# RPI3_LVDS.net
KiCad netlist of a schematic drawn in EAGLE
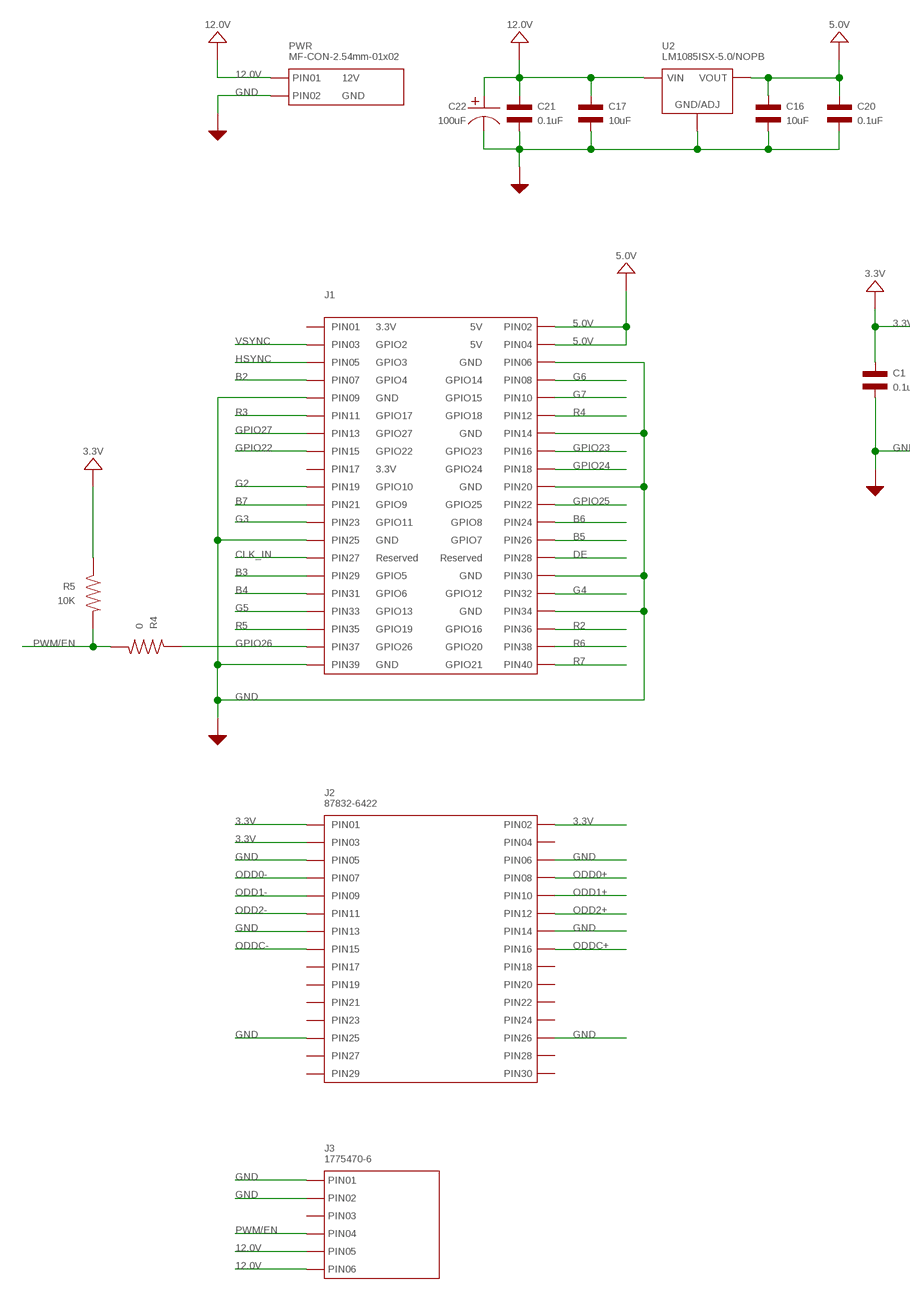
[diagram p0: schematic, sheet 1, part 1 of 2]
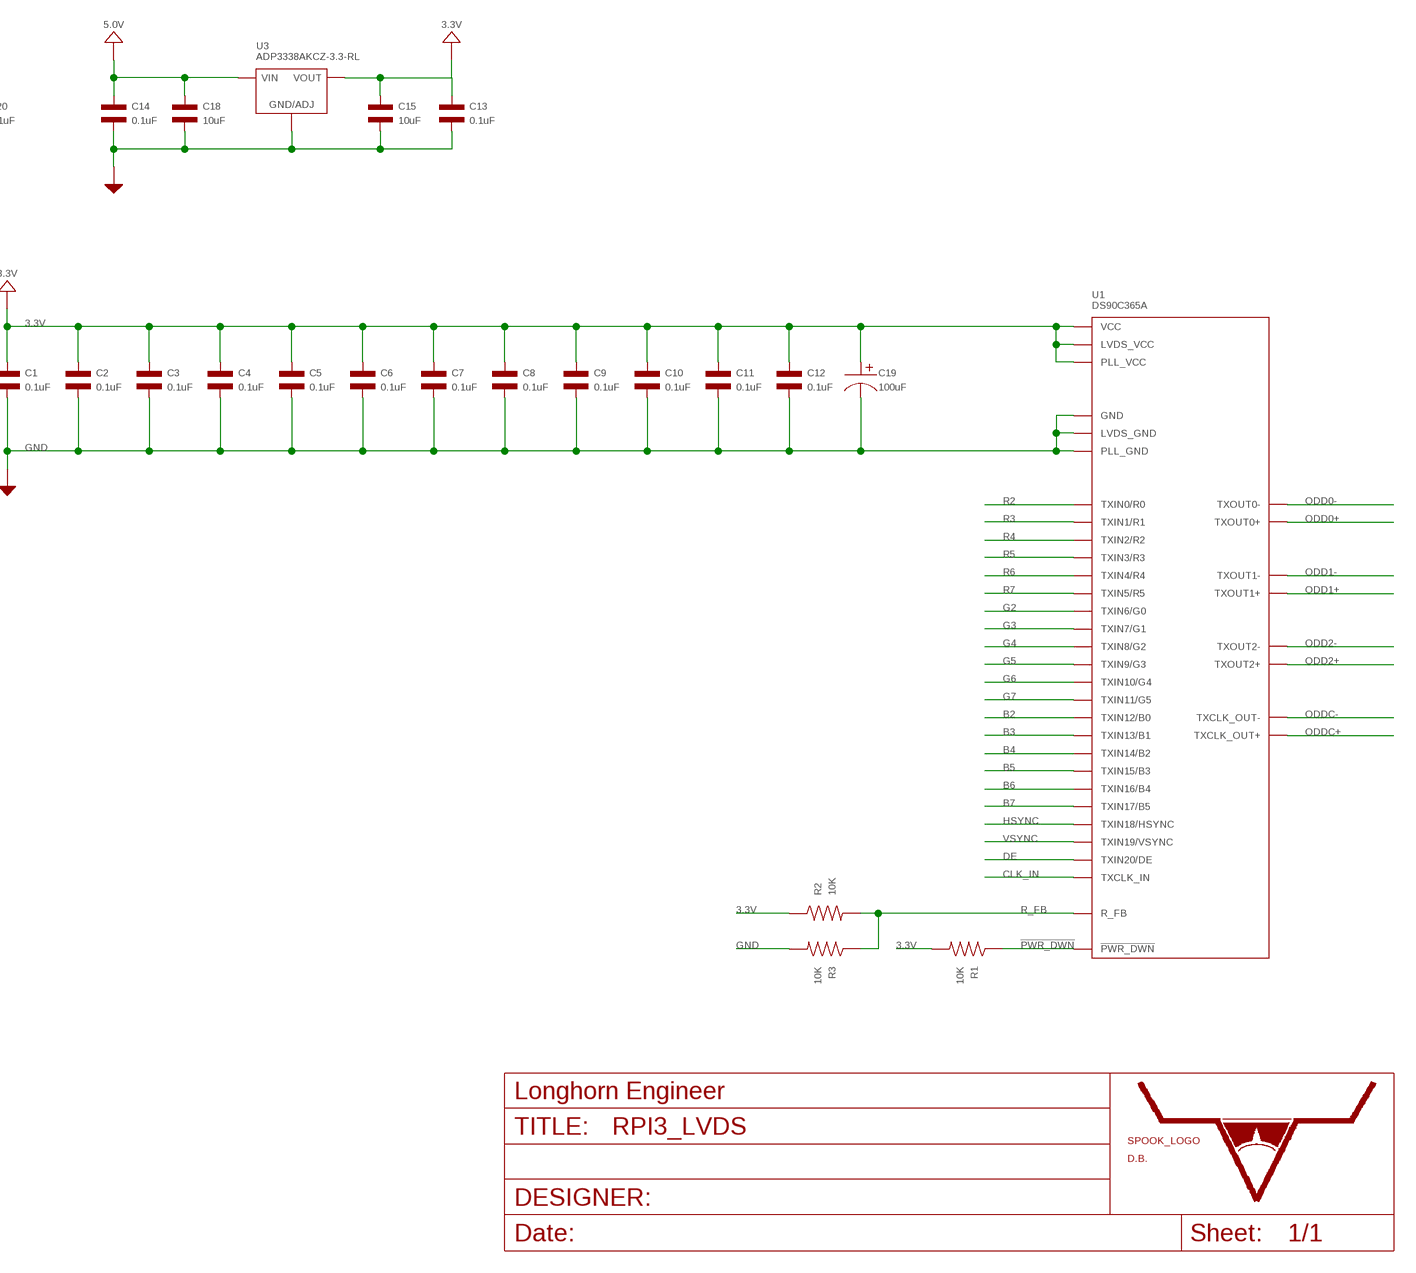
[diagram p1: schematic, sheet 1, part 2 of 2]

(export (version "E")
  (design (tool "Eeschema 10.0.6"))
  (components
    (comp (ref "C1")
      (value "0.1uF")
      (footprint "eagle-import:C0603")
      (libsource (lib "eagle-import") (part "CAPACITOR_NP_0603"))
    )
    (comp (ref "C2")
      (value "0.1uF")
      (footprint "eagle-import:C0603")
      (libsource (lib "eagle-import") (part "CAPACITOR_NP_0603"))
    )
    (comp (ref "C3")
      (value "0.1uF")
      (footprint "eagle-import:C0603")
      (libsource (lib "eagle-import") (part "CAPACITOR_NP_0603"))
    )
    (comp (ref "C4")
      (value "0.1uF")
      (footprint "eagle-import:C0603")
      (libsource (lib "eagle-import") (part "CAPACITOR_NP_0603"))
    )
    (comp (ref "C5")
      (value "0.1uF")
      (footprint "eagle-import:C0603")
      (libsource (lib "eagle-import") (part "CAPACITOR_NP_0603"))
    )
    (comp (ref "C6")
      (value "0.1uF")
      (footprint "eagle-import:C0603")
      (libsource (lib "eagle-import") (part "CAPACITOR_NP_0603"))
    )
    (comp (ref "C7")
      (value "0.1uF")
      (footprint "eagle-import:C0603")
      (libsource (lib "eagle-import") (part "CAPACITOR_NP_0603"))
    )
    (comp (ref "C8")
      (value "0.1uF")
      (footprint "eagle-import:C0603")
      (libsource (lib "eagle-import") (part "CAPACITOR_NP_0603"))
    )
    (comp (ref "C9")
      (value "0.1uF")
      (footprint "eagle-import:C0603")
      (libsource (lib "eagle-import") (part "CAPACITOR_NP_0603"))
    )
    (comp (ref "C10")
      (value "0.1uF")
      (footprint "eagle-import:C0603")
      (libsource (lib "eagle-import") (part "CAPACITOR_NP_0603"))
    )
    (comp (ref "C11")
      (value "0.1uF")
      (footprint "eagle-import:C0603")
      (libsource (lib "eagle-import") (part "CAPACITOR_NP_0603"))
    )
    (comp (ref "C12")
      (value "0.1uF")
      (footprint "eagle-import:C0603")
      (libsource (lib "eagle-import") (part "CAPACITOR_NP_0603"))
    )
    (comp (ref "C13")
      (value "0.1uF")
      (footprint "eagle-import:C0603")
      (libsource (lib "eagle-import") (part "CAPACITOR_NP_0603"))
    )
    (comp (ref "C14")
      (value "0.1uF")
      (footprint "eagle-import:C0603")
      (libsource (lib "eagle-import") (part "CAPACITOR_NP_0603"))
    )
    (comp (ref "C15")
      (value "10uF")
      (footprint "eagle-import:C1206")
      (libsource (lib "eagle-import") (part "CAPACITOR_NP_1206"))
    )
    (comp (ref "C16")
      (value "10uF")
      (footprint "eagle-import:C1206")
      (libsource (lib "eagle-import") (part "CAPACITOR_NP_1206"))
    )
    (comp (ref "C17")
      (value "10uF")
      (footprint "eagle-import:C1206")
      (libsource (lib "eagle-import") (part "CAPACITOR_NP_1206"))
    )
    (comp (ref "C18")
      (value "10uF")
      (footprint "eagle-import:C1206")
      (libsource (lib "eagle-import") (part "CAPACITOR_NP_1206"))
    )
    (comp (ref "C19")
      (value "100uF")
      (footprint "eagle-import:CP6.3MM")
      (libsource (lib "eagle-import") (part "CAPACITOR_P_6.3MM"))
    )
    (comp (ref "C20")
      (value "0.1uF")
      (footprint "eagle-import:C0603")
      (libsource (lib "eagle-import") (part "CAPACITOR_NP_0603"))
    )
    (comp (ref "C21")
      (value "0.1uF")
      (footprint "eagle-import:C0603")
      (libsource (lib "eagle-import") (part "CAPACITOR_NP_0603"))
    )
    (comp (ref "C22")
      (value "100uF")
      (footprint "eagle-import:CP6.3MM")
      (libsource (lib "eagle-import") (part "CAPACITOR_P_6.3MM"))
    )
    (comp (ref "J1")
      (value "CON_02X202.54MM_PIN_HEADER")
      (footprint "eagle-import:2.54MM_02X20_PIN_HEADER")
      (fields
        (field (name "LABEL01") "3.3V")
        (field (name "LABEL02") "5V")
        (field (name "LABEL03") "GPIO2")
        (field (name "LABEL04") "5V")
        (field (name "LABEL05") "GPIO3")
        (field (name "LABEL06") "GND")
        (field (name "LABEL07") "GPIO4")
        (field (name "LABEL08") "GPIO14")
        (field (name "LABEL09") "GND")
        (field (name "LABEL10") "GPIO15")
        (field (name "LABEL11") "GPIO17")
        (field (name "LABEL12") "GPIO18")
        (field (name "LABEL13") "GPIO27")
        (field (name "LABEL14") "GND")
        (field (name "LABEL15") "GPIO22")
        (field (name "LABEL16") "GPIO23")
        (field (name "LABEL17") "3.3V")
        (field (name "LABEL18") "GPIO24")
        (field (name "LABEL19") "GPIO10")
        (field (name "LABEL20") "GND")
        (field (name "LABEL21") "GPIO9")
        (field (name "LABEL22") "GPIO25")
        (field (name "LABEL23") "GPIO11")
        (field (name "LABEL24") "GPIO8")
        (field (name "LABEL25") "GND")
        (field (name "LABEL26") "GPIO7")
        (field (name "LABEL27") "Reserved")
        (field (name "LABEL28") "Reserved")
        (field (name "LABEL29") "GPIO5")
        (field (name "LABEL30") "GND")
        (field (name "LABEL31") "GPIO6")
        (field (name "LABEL32") "GPIO12")
        (field (name "LABEL33") "GPIO13")
        (field (name "LABEL34") "GND")
        (field (name "LABEL35") "GPIO19")
        (field (name "LABEL36") "GPIO16")
        (field (name "LABEL37") "GPIO26")
        (field (name "LABEL38") "GPIO20")
        (field (name "LABEL39") "GND")
        (field (name "LABEL40") "GPIO21")
      )
      (libsource (lib "eagle-import") (part "CON_02X202.54MM_PIN_HEADER"))
    )
    (comp (ref "J2")
      (value "87832-6422")
      (footprint "eagle-import:87832-6422")
      (libsource (lib "eagle-import") (part "CON_02X15_87832-6422"))
    )
    (comp (ref "J3")
      (value "1775470-6")
      (footprint "eagle-import:1775470-6")
      (libsource (lib "eagle-import") (part "CON_01X06_1775470-6"))
    )
    (comp (ref "LOGO1")
      (value "SPOOKY_LOGOSPOOKY_LOGO")
      (footprint "eagle-import:SPOOKY_LOGO")
      (libsource (lib "eagle-import") (part "SPOOKY_LOGOSPOOKY_LOGO"))
    )
    (comp (ref "PWR")
      (value "MF-CON-2.54mm-01x02")
      (footprint "eagle-import:PTH_2.54MM_01X02")
      (fields (field (name "HOUSEPART") "YES") (field (name "LABEL01") "12V") (field (name "LABEL02") "GND"))
      (libsource (lib "eagle-import") (part "CON_01X02_PTH_2.54MM"))
    )
    (comp (ref "R1")
      (value "10K")
      (footprint "eagle-import:R0603")
      (libsource (lib "eagle-import") (part "RESISTOR_0603"))
    )
    (comp (ref "R2")
      (value "10K")
      (footprint "eagle-import:R0603")
      (libsource (lib "eagle-import") (part "RESISTOR_0603"))
    )
    (comp (ref "R3")
      (value "10K")
      (footprint "eagle-import:R0603")
      (libsource (lib "eagle-import") (part "RESISTOR_0603"))
    )
    (comp (ref "R4")
      (value "0")
      (footprint "eagle-import:R0603")
      (libsource (lib "eagle-import") (part "RESISTOR_0603"))
    )
    (comp (ref "R5")
      (value "10K")
      (footprint "eagle-import:R0603")
      (libsource (lib "eagle-import") (part "RESISTOR_0603"))
    )
    (comp (ref "U$14")
      (value "LHE_FRAME")
      (footprint "eagle-import:LHE_FRAME")
      (fields (field (name "DNAME") "Parker Dillmann") (field (name "REVNUM") "REV: 3"))
      (libsource (lib "eagle-import") (part "LHE_FRAME"))
    )
    (comp (ref "U$15")
      (value "DB_LOGO_SILK_MEDIUM")
      (footprint "eagle-import:DB_SILK_MEDIUM")
      (libsource (lib "eagle-import") (part "DB_LOGO_SILK_MEDIUM"))
    )
    (comp (ref "U1")
      (value "DS90C365A")
      (footprint "eagle-import:DS90C365A_TSSOP-48")
      (libsource (lib "eagle-import") (part "DS90C365A"))
    )
    (comp (ref "U2")
      (value "LM1085ISX-5.0/NOPB")
      (footprint "eagle-import:LM1085_TO-263-3")
      (libsource (lib "eagle-import") (part "LINEAR_VOTLAGE_REGULATORS_LM1085"))
    )
    (comp (ref "U3")
      (value "ADP3338AKCZ-3.3-RL")
      (footprint "eagle-import:ADP3338_SOT-223-3")
      (libsource (lib "eagle-import") (part "LINEAR_VOTLAGE_REGULATORS_ADP3338"))
    )
  )
  (nets
    (net (code "1") (name "/B2") (class "Default")
      (node (ref "J1") (pin "7") (pinfunction "7_7") (pintype "bidirectional"))
      (node (ref "U1") (pin "P$13") (pinfunction "TXIN12/B0_P$13") (pintype "bidirectional"))
    )
    (net (code "2") (name "/B3") (class "Default")
      (node (ref "J1") (pin "29") (pinfunction "29_29") (pintype "bidirectional"))
      (node (ref "U1") (pin "P$15") (pinfunction "TXIN13/B1_P$15") (pintype "bidirectional"))
    )
    (net (code "3") (name "/B4") (class "Default")
      (node (ref "J1") (pin "31") (pinfunction "31_31") (pintype "bidirectional"))
      (node (ref "U1") (pin "P$16") (pinfunction "TXIN14/B2_P$16") (pintype "bidirectional"))
    )
    (net (code "4") (name "/B5") (class "Default")
      (node (ref "J1") (pin "26") (pinfunction "26_26") (pintype "bidirectional"))
      (node (ref "U1") (pin "P$18") (pinfunction "TXIN15/B3_P$18") (pintype "bidirectional"))
    )
    (net (code "5") (name "/B6") (class "Default")
      (node (ref "J1") (pin "24") (pinfunction "24_24") (pintype "bidirectional"))
      (node (ref "U1") (pin "P$19") (pinfunction "TXIN16/B4_P$19") (pintype "bidirectional"))
    )
    (net (code "6") (name "/B7") (class "Default")
      (node (ref "J1") (pin "21") (pinfunction "21_21") (pintype "bidirectional"))
      (node (ref "U1") (pin "P$20") (pinfunction "TXIN17/B5_P$20") (pintype "bidirectional"))
    )
    (net (code "7") (name "/CLK_IN") (class "Default")
      (node (ref "J1") (pin "27") (pinfunction "27_27") (pintype "bidirectional"))
      (node (ref "U1") (pin "P$26") (pinfunction "TXCLK_IN_P$26") (pintype "bidirectional"))
    )
    (net (code "8") (name "/DE") (class "Default")
      (node (ref "J1") (pin "28") (pinfunction "28_28") (pintype "bidirectional"))
      (node (ref "U1") (pin "P$25") (pinfunction "TXIN20/DE_P$25") (pintype "bidirectional"))
    )
    (net (code "9") (name "/G2") (class "Default")
      (node (ref "J1") (pin "19") (pinfunction "19_19") (pintype "bidirectional"))
      (node (ref "U1") (pin "P$4") (pinfunction "TXIN6/G0_P$4") (pintype "bidirectional"))
    )
    (net (code "10") (name "/G3") (class "Default")
      (node (ref "J1") (pin "23") (pinfunction "23_23") (pintype "bidirectional"))
      (node (ref "U1") (pin "P$6") (pinfunction "TXIN7/G1_P$6") (pintype "bidirectional"))
    )
    (net (code "11") (name "/G4") (class "Default")
      (node (ref "J1") (pin "32") (pinfunction "32_32") (pintype "bidirectional"))
      (node (ref "U1") (pin "P$7") (pinfunction "TXIN8/G2_P$7") (pintype "bidirectional"))
    )
    (net (code "12") (name "/G5") (class "Default")
      (node (ref "J1") (pin "33") (pinfunction "33_33") (pintype "bidirectional"))
      (node (ref "U1") (pin "P$9") (pinfunction "TXIN9/G3_P$9") (pintype "bidirectional"))
    )
    (net (code "13") (name "/G6") (class "Default")
      (node (ref "J1") (pin "8") (pinfunction "8_8") (pintype "bidirectional"))
      (node (ref "U1") (pin "P$10") (pinfunction "TXIN10/G4_P$10") (pintype "bidirectional"))
    )
    (net (code "14") (name "/G7") (class "Default")
      (node (ref "J1") (pin "10") (pinfunction "10_10") (pintype "bidirectional"))
      (node (ref "U1") (pin "P$12") (pinfunction "TXIN11/G5_P$12") (pintype "bidirectional"))
    )
    (net (code "15") (name "/GPIO22") (class "Default")
      (node (ref "J1") (pin "15") (pinfunction "15_15") (pintype "bidirectional"))
    )
    (net (code "16") (name "/GPIO23") (class "Default")
      (node (ref "J1") (pin "16") (pinfunction "16_16") (pintype "bidirectional"))
    )
    (net (code "17") (name "/GPIO24") (class "Default")
      (node (ref "J1") (pin "18") (pinfunction "18_18") (pintype "bidirectional"))
    )
    (net (code "18") (name "/GPIO25") (class "Default")
      (node (ref "J1") (pin "22") (pinfunction "22_22") (pintype "bidirectional"))
    )
    (net (code "19") (name "/GPIO26") (class "Default")
      (node (ref "J1") (pin "37") (pinfunction "37_37") (pintype "bidirectional"))
      (node (ref "R4") (pin "P$1") (pinfunction "P$1_P$1") (pintype "passive"))
    )
    (net (code "20") (name "/GPIO27") (class "Default")
      (node (ref "J1") (pin "13") (pinfunction "13_13") (pintype "bidirectional"))
    )
    (net (code "21") (name "/HSYNC") (class "Default")
      (node (ref "J1") (pin "5") (pinfunction "5_5") (pintype "bidirectional"))
      (node (ref "U1") (pin "P$22") (pinfunction "TXIN18/HSYNC_P$22") (pintype "bidirectional"))
    )
    (net (code "22") (name "/ODD0+") (class "Default")
      (node (ref "J2") (pin "P$8") (pinfunction "PIN7_P$8") (pintype "bidirectional"))
      (node (ref "U1") (pin "P$40") (pinfunction "TXOUT0+_P$40") (pintype "bidirectional"))
    )
    (net (code "23") (name "/ODD0-") (class "Default")
      (node (ref "J2") (pin "P$7") (pinfunction "PIN6_P$7") (pintype "bidirectional"))
      (node (ref "U1") (pin "P$41") (pinfunction "TXOUT0-_P$41") (pintype "bidirectional"))
    )
    (net (code "24") (name "/ODD1+") (class "Default")
      (node (ref "J2") (pin "P$10") (pinfunction "PIN9_P$10") (pintype "bidirectional"))
      (node (ref "U1") (pin "P$38") (pinfunction "TXOUT1+_P$38") (pintype "bidirectional"))
    )
    (net (code "25") (name "/ODD1-") (class "Default")
      (node (ref "J2") (pin "P$9") (pinfunction "PIN8_P$9") (pintype "bidirectional"))
      (node (ref "U1") (pin "P$39") (pinfunction "TXOUT1-_P$39") (pintype "bidirectional"))
    )
    (net (code "26") (name "/ODD2+") (class "Default")
      (node (ref "J2") (pin "P$12") (pinfunction "PIN11_P$12") (pintype "bidirectional"))
      (node (ref "U1") (pin "P$34") (pinfunction "TXOUT2+_P$34") (pintype "bidirectional"))
    )
    (net (code "27") (name "/ODD2-") (class "Default")
      (node (ref "J2") (pin "P$11") (pinfunction "PIN10_P$11") (pintype "bidirectional"))
      (node (ref "U1") (pin "P$35") (pinfunction "TXOUT2-_P$35") (pintype "bidirectional"))
    )
    (net (code "28") (name "/ODDC+") (class "Default")
      (node (ref "J2") (pin "P$16") (pinfunction "PIN15_P$16") (pintype "bidirectional"))
      (node (ref "U1") (pin "P$32") (pinfunction "TXCLK_OUT+_P$32") (pintype "bidirectional"))
    )
    (net (code "29") (name "/ODDC-") (class "Default")
      (node (ref "J2") (pin "P$15") (pinfunction "PIN14_P$15") (pintype "bidirectional"))
      (node (ref "U1") (pin "P$33") (pinfunction "TXCLK_OUT-_P$33") (pintype "bidirectional"))
    )
    (net (code "30") (name "/PWM{slash}EN") (class "Default")
      (node (ref "J3") (pin "P$4") (pinfunction "4_P$4") (pintype "passive"))
      (node (ref "R4") (pin "P$2") (pinfunction "P$2_P$2") (pintype "passive"))
      (node (ref "R5") (pin "P$2") (pinfunction "P$2_P$2") (pintype "passive"))
    )
    (net (code "31") (name "/R2") (class "Default")
      (node (ref "J1") (pin "36") (pinfunction "36_36") (pintype "bidirectional"))
      (node (ref "U1") (pin "P$44") (pinfunction "TXIN0/R0_P$44") (pintype "bidirectional"))
    )
    (net (code "32") (name "/R3") (class "Default")
      (node (ref "J1") (pin "11") (pinfunction "11_11") (pintype "bidirectional"))
      (node (ref "U1") (pin "P$45") (pinfunction "TXIN1/R1_P$45") (pintype "bidirectional"))
    )
    (net (code "33") (name "/R4") (class "Default")
      (node (ref "J1") (pin "12") (pinfunction "12_12") (pintype "bidirectional"))
      (node (ref "U1") (pin "P$47") (pinfunction "TXIN2/R2_P$47") (pintype "bidirectional"))
    )
    (net (code "34") (name "/R5") (class "Default")
      (node (ref "J1") (pin "35") (pinfunction "35_35") (pintype "bidirectional"))
      (node (ref "U1") (pin "P$48") (pinfunction "TXIN3/R3_P$48") (pintype "bidirectional"))
    )
    (net (code "35") (name "/R6") (class "Default")
      (node (ref "J1") (pin "38") (pinfunction "38_38") (pintype "bidirectional"))
      (node (ref "U1") (pin "P$1") (pinfunction "TXIN4/R4_P$1") (pintype "bidirectional"))
    )
    (net (code "36") (name "/R7") (class "Default")
      (node (ref "J1") (pin "40") (pinfunction "40_40") (pintype "bidirectional"))
      (node (ref "U1") (pin "P$3") (pinfunction "TXIN5/R5_P$3") (pintype "bidirectional"))
    )
    (net (code "37") (name "/R_FB") (class "Default")
      (node (ref "R2") (pin "P$2") (pinfunction "P$2_P$2") (pintype "passive"))
      (node (ref "R3") (pin "P$1") (pinfunction "P$1_P$1") (pintype "passive"))
      (node (ref "U1") (pin "P$14") (pinfunction "R_FB_P$14") (pintype "bidirectional"))
    )
    (net (code "38") (name "/VSYNC") (class "Default")
      (node (ref "J1") (pin "3") (pinfunction "3_3") (pintype "bidirectional"))
      (node (ref "U1") (pin "P$23") (pinfunction "TXIN19/VSYNC_P$23") (pintype "bidirectional"))
    )
    (net (code "39") (name "/~{PWR_DWN}") (class "Default")
      (node (ref "R1") (pin "P$1") (pinfunction "P$1_P$1") (pintype "passive"))
      (node (ref "U1") (pin "P$27") (pinfunction "~{PWR_DWN}_P$27") (pintype "bidirectional"))
    )
    (net (code "40") (name "3.3V") (class "Default")
      (node (ref "C1") (pin "P$1") (pinfunction "P$1_P$1") (pintype "passive"))
      (node (ref "C10") (pin "P$1") (pinfunction "P$1_P$1") (pintype "passive"))
      (node (ref "C11") (pin "P$1") (pinfunction "P$1_P$1") (pintype "passive"))
      (node (ref "C12") (pin "P$1") (pinfunction "P$1_P$1") (pintype "passive"))
      (node (ref "C13") (pin "P$1") (pinfunction "P$1_P$1") (pintype "passive"))
      (node (ref "C15") (pin "P$1") (pinfunction "P$1_P$1") (pintype "passive"))
      (node (ref "C19") (pin "P$1") (pinfunction "P$1_P$1") (pintype "passive"))
      (node (ref "C2") (pin "P$1") (pinfunction "P$1_P$1") (pintype "passive"))
      (node (ref "C3") (pin "P$1") (pinfunction "P$1_P$1") (pintype "passive"))
      (node (ref "C4") (pin "P$1") (pinfunction "P$1_P$1") (pintype "passive"))
      (node (ref "C5") (pin "P$1") (pinfunction "P$1_P$1") (pintype "passive"))
      (node (ref "C6") (pin "P$1") (pinfunction "P$1_P$1") (pintype "passive"))
      (node (ref "C7") (pin "P$1") (pinfunction "P$1_P$1") (pintype "passive"))
      (node (ref "C8") (pin "P$1") (pinfunction "P$1_P$1") (pintype "passive"))
      (node (ref "C9") (pin "P$1") (pinfunction "P$1_P$1") (pintype "passive"))
      (node (ref "J2") (pin "P$1") (pinfunction "PIN0_P$1") (pintype "bidirectional"))
      (node (ref "J2") (pin "P$2") (pinfunction "PIN1_P$2") (pintype "bidirectional"))
      (node (ref "J2") (pin "P$3") (pinfunction "PIN2_P$3") (pintype "bidirectional"))
      (node (ref "R1") (pin "P$2") (pinfunction "P$2_P$2") (pintype "passive"))
      (node (ref "R2") (pin "P$1") (pinfunction "P$1_P$1") (pintype "passive"))
      (node (ref "R5") (pin "P$1") (pinfunction "P$1_P$1") (pintype "passive"))
      (node (ref "U1") (pin "P$2") (pinfunction "VCC_P$2") (pintype "bidirectional"))
      (node (ref "U1") (pin "P$21") (pinfunction "VCC_P$21") (pintype "bidirectional"))
      (node (ref "U1") (pin "P$29") (pinfunction "PLL_VCC_P$29") (pintype "bidirectional"))
      (node (ref "U1") (pin "P$37") (pinfunction "LVDS_VCC_P$37") (pintype "bidirectional"))
      (node (ref "U1") (pin "P$8") (pinfunction "VCC_P$8") (pintype "bidirectional"))
      (node (ref "U3") (pin "2") (pinfunction "OUT_2") (pintype "bidirectional"))
      (node (ref "U3") (pin "PAD") (pinfunction "OUT_PAD") (pintype "bidirectional"))
    )
    (net (code "41") (name "5.0V") (class "Default")
      (node (ref "C14") (pin "P$1") (pinfunction "P$1_P$1") (pintype "passive"))
      (node (ref "C16") (pin "P$1") (pinfunction "P$1_P$1") (pintype "passive"))
      (node (ref "C18") (pin "P$1") (pinfunction "P$1_P$1") (pintype "passive"))
      (node (ref "C20") (pin "P$1") (pinfunction "P$1_P$1") (pintype "passive"))
      (node (ref "J1") (pin "2") (pinfunction "2_2") (pintype "bidirectional"))
      (node (ref "J1") (pin "4") (pinfunction "4_4") (pintype "bidirectional"))
      (node (ref "U2") (pin "P$2") (pinfunction "OUT_P$2") (pintype "bidirectional"))
      (node (ref "U2") (pin "P$4") (pinfunction "OUT_P$4") (pintype "bidirectional"))
      (node (ref "U3") (pin "3") (pinfunction "IN_3") (pintype "bidirectional"))
    )
    (net (code "42") (name "12.0V") (class "Default")
      (node (ref "C17") (pin "P$1") (pinfunction "P$1_P$1") (pintype "passive"))
      (node (ref "C21") (pin "P$1") (pinfunction "P$1_P$1") (pintype "passive"))
      (node (ref "C22") (pin "P$1") (pinfunction "P$1_P$1") (pintype "passive"))
      (node (ref "J3") (pin "P$5") (pinfunction "5_P$5") (pintype "passive"))
      (node (ref "J3") (pin "P$6") (pinfunction "6_P$6") (pintype "passive"))
      (node (ref "PWR") (pin "P$1") (pinfunction "PIN1_P$1") (pintype "bidirectional"))
      (node (ref "U2") (pin "P$3") (pinfunction "IN_P$3") (pintype "bidirectional"))
    )
    (net (code "43") (name "GND_RAIL") (class "Default")
      (node (ref "C1") (pin "P$2") (pinfunction "P$2_P$2") (pintype "passive"))
      (node (ref "C10") (pin "P$2") (pinfunction "P$2_P$2") (pintype "passive"))
      (node (ref "C11") (pin "P$2") (pinfunction "P$2_P$2") (pintype "passive"))
      (node (ref "C12") (pin "P$2") (pinfunction "P$2_P$2") (pintype "passive"))
      (node (ref "C13") (pin "P$2") (pinfunction "P$2_P$2") (pintype "passive"))
      (node (ref "C14") (pin "P$2") (pinfunction "P$2_P$2") (pintype "passive"))
      (node (ref "C15") (pin "P$2") (pinfunction "P$2_P$2") (pintype "passive"))
      (node (ref "C16") (pin "P$2") (pinfunction "P$2_P$2") (pintype "passive"))
      (node (ref "C17") (pin "P$2") (pinfunction "P$2_P$2") (pintype "passive"))
      (node (ref "C18") (pin "P$2") (pinfunction "P$2_P$2") (pintype "passive"))
      (node (ref "C19") (pin "P$2") (pinfunction "P$2_P$2") (pintype "passive"))
      (node (ref "C2") (pin "P$2") (pinfunction "P$2_P$2") (pintype "passive"))
      (node (ref "C20") (pin "P$2") (pinfunction "P$2_P$2") (pintype "passive"))
      (node (ref "C21") (pin "P$2") (pinfunction "P$2_P$2") (pintype "passive"))
      (node (ref "C22") (pin "P$2") (pinfunction "P$2_P$2") (pintype "passive"))
      (node (ref "C3") (pin "P$2") (pinfunction "P$2_P$2") (pintype "passive"))
      (node (ref "C4") (pin "P$2") (pinfunction "P$2_P$2") (pintype "passive"))
      (node (ref "C5") (pin "P$2") (pinfunction "P$2_P$2") (pintype "passive"))
      (node (ref "C6") (pin "P$2") (pinfunction "P$2_P$2") (pintype "passive"))
      (node (ref "C7") (pin "P$2") (pinfunction "P$2_P$2") (pintype "passive"))
      (node (ref "C8") (pin "P$2") (pinfunction "P$2_P$2") (pintype "passive"))
      (node (ref "C9") (pin "P$2") (pinfunction "P$2_P$2") (pintype "passive"))
      (node (ref "J1") (pin "14") (pinfunction "14_14") (pintype "bidirectional"))
      (node (ref "J1") (pin "20") (pinfunction "20_20") (pintype "bidirectional"))
      (node (ref "J1") (pin "25") (pinfunction "25_25") (pintype "bidirectional"))
      (node (ref "J1") (pin "30") (pinfunction "30_30") (pintype "bidirectional"))
      (node (ref "J1") (pin "34") (pinfunction "34_34") (pintype "bidirectional"))
      (node (ref "J1") (pin "39") (pinfunction "39_39") (pintype "bidirectional"))
      (node (ref "J1") (pin "6") (pinfunction "6_6") (pintype "bidirectional"))
      (node (ref "J1") (pin "9") (pinfunction "9_9") (pintype "bidirectional"))
      (node (ref "J2") (pin "P$13") (pinfunction "PIN12_P$13") (pintype "bidirectional"))
      (node (ref "J2") (pin "P$14") (pinfunction "PIN13_P$14") (pintype "bidirectional"))
      (node (ref "J2") (pin "P$25") (pinfunction "PIN24_P$25") (pintype "bidirectional"))
      (node (ref "J2") (pin "P$26") (pinfunction "PIN25_P$26") (pintype "bidirectional"))
      (node (ref "J2") (pin "P$5") (pinfunction "PIN4_P$5") (pintype "bidirectional"))
      (node (ref "J2") (pin "P$6") (pinfunction "PIN5_P$6") (pintype "bidirectional"))
      (node (ref "J3") (pin "P$1") (pinfunction "1_P$1") (pintype "passive"))
      (node (ref "J3") (pin "P$2") (pinfunction "2_P$2") (pintype "passive"))
      (node (ref "PWR") (pin "P$2") (pinfunction "PIN2_P$2") (pintype "bidirectional"))
      (node (ref "R3") (pin "P$2") (pinfunction "P$2_P$2") (pintype "passive"))
      (node (ref "U1") (pin "P$11") (pinfunction "GND_P$11") (pintype "bidirectional"))
      (node (ref "U1") (pin "P$17") (pinfunction "GND_P$17") (pintype "bidirectional"))
      (node (ref "U1") (pin "P$24") (pinfunction "GND_P$24") (pintype "bidirectional"))
      (node (ref "U1") (pin "P$28") (pinfunction "PLL_GND_P$28") (pintype "bidirectional"))
      (node (ref "U1") (pin "P$30") (pinfunction "PLL_GND_P$30") (pintype "bidirectional"))
      (node (ref "U1") (pin "P$31") (pinfunction "LVDS_GND_P$31") (pintype "bidirectional"))
      (node (ref "U1") (pin "P$36") (pinfunction "LVDS_GND_P$36") (pintype "bidirectional"))
      (node (ref "U1") (pin "P$42") (pinfunction "LVDS_GND_P$42") (pintype "bidirectional"))
      (node (ref "U1") (pin "P$46") (pinfunction "GND_P$46") (pintype "bidirectional"))
      (node (ref "U1") (pin "P$5") (pinfunction "GND_P$5") (pintype "bidirectional"))
      (node (ref "U2") (pin "P$1") (pinfunction "GND_P$1") (pintype "bidirectional"))
      (node (ref "U3") (pin "1") (pinfunction "GND_1") (pintype "bidirectional"))
    )
    (net (code "44") (name "unconnected-(J1-Pad1)") (class "Default")
      (node (ref "J1") (pin "1") (pinfunction "1_1") (pintype "bidirectional"))
    )
    (net (code "45") (name "unconnected-(J1-Pad17)") (class "Default")
      (node (ref "J1") (pin "17") (pinfunction "17_17") (pintype "bidirectional"))
    )
    (net (code "46") (name "unconnected-(J2-PIN3-PadP$4)") (class "Default")
      (node (ref "J2") (pin "P$4") (pinfunction "PIN3_P$4") (pintype "bidirectional"))
    )
    (net (code "47") (name "unconnected-(J2-PIN16-PadP$17)") (class "Default")
      (node (ref "J2") (pin "P$17") (pinfunction "PIN16_P$17") (pintype "bidirectional"))
    )
    (net (code "48") (name "unconnected-(J2-PIN17-PadP$18)") (class "Default")
      (node (ref "J2") (pin "P$18") (pinfunction "PIN17_P$18") (pintype "bidirectional"))
    )
    (net (code "49") (name "unconnected-(J2-PIN18-PadP$19)") (class "Default")
      (node (ref "J2") (pin "P$19") (pinfunction "PIN18_P$19") (pintype "bidirectional"))
    )
    (net (code "50") (name "unconnected-(J2-PIN19-PadP$20)") (class "Default")
      (node (ref "J2") (pin "P$20") (pinfunction "PIN19_P$20") (pintype "bidirectional"))
    )
    (net (code "51") (name "unconnected-(J2-PIN20-PadP$21)") (class "Default")
      (node (ref "J2") (pin "P$21") (pinfunction "PIN20_P$21") (pintype "bidirectional"))
    )
    (net (code "52") (name "unconnected-(J2-PIN21-PadP$22)") (class "Default")
      (node (ref "J2") (pin "P$22") (pinfunction "PIN21_P$22") (pintype "bidirectional"))
    )
    (net (code "53") (name "unconnected-(J2-PIN22-PadP$23)") (class "Default")
      (node (ref "J2") (pin "P$23") (pinfunction "PIN22_P$23") (pintype "bidirectional"))
    )
    (net (code "54") (name "unconnected-(J2-PIN23-PadP$24)") (class "Default")
      (node (ref "J2") (pin "P$24") (pinfunction "PIN23_P$24") (pintype "bidirectional"))
    )
    (net (code "55") (name "unconnected-(J2-PIN26-PadP$27)") (class "Default")
      (node (ref "J2") (pin "P$27") (pinfunction "PIN26_P$27") (pintype "bidirectional"))
    )
    (net (code "56") (name "unconnected-(J2-PIN27-PadP$28)") (class "Default")
      (node (ref "J2") (pin "P$28") (pinfunction "PIN27_P$28") (pintype "bidirectional"))
    )
    (net (code "57") (name "unconnected-(J2-PIN28-PadP$29)") (class "Default")
      (node (ref "J2") (pin "P$29") (pinfunction "PIN28_P$29") (pintype "bidirectional"))
    )
    (net (code "58") (name "unconnected-(J2-PIN29-PadP$30)") (class "Default")
      (node (ref "J2") (pin "P$30") (pinfunction "PIN29_P$30") (pintype "bidirectional"))
    )
    (net (code "59") (name "unconnected-(J3-3-PadP$3)") (class "Default")
      (node (ref "J3") (pin "P$3") (pinfunction "3_P$3") (pintype "passive"))
    )
  )
)
